# PG03_Schematic_Sheet1_ECO.net
KiCad netlist of a schematic drawn in Altium Designer
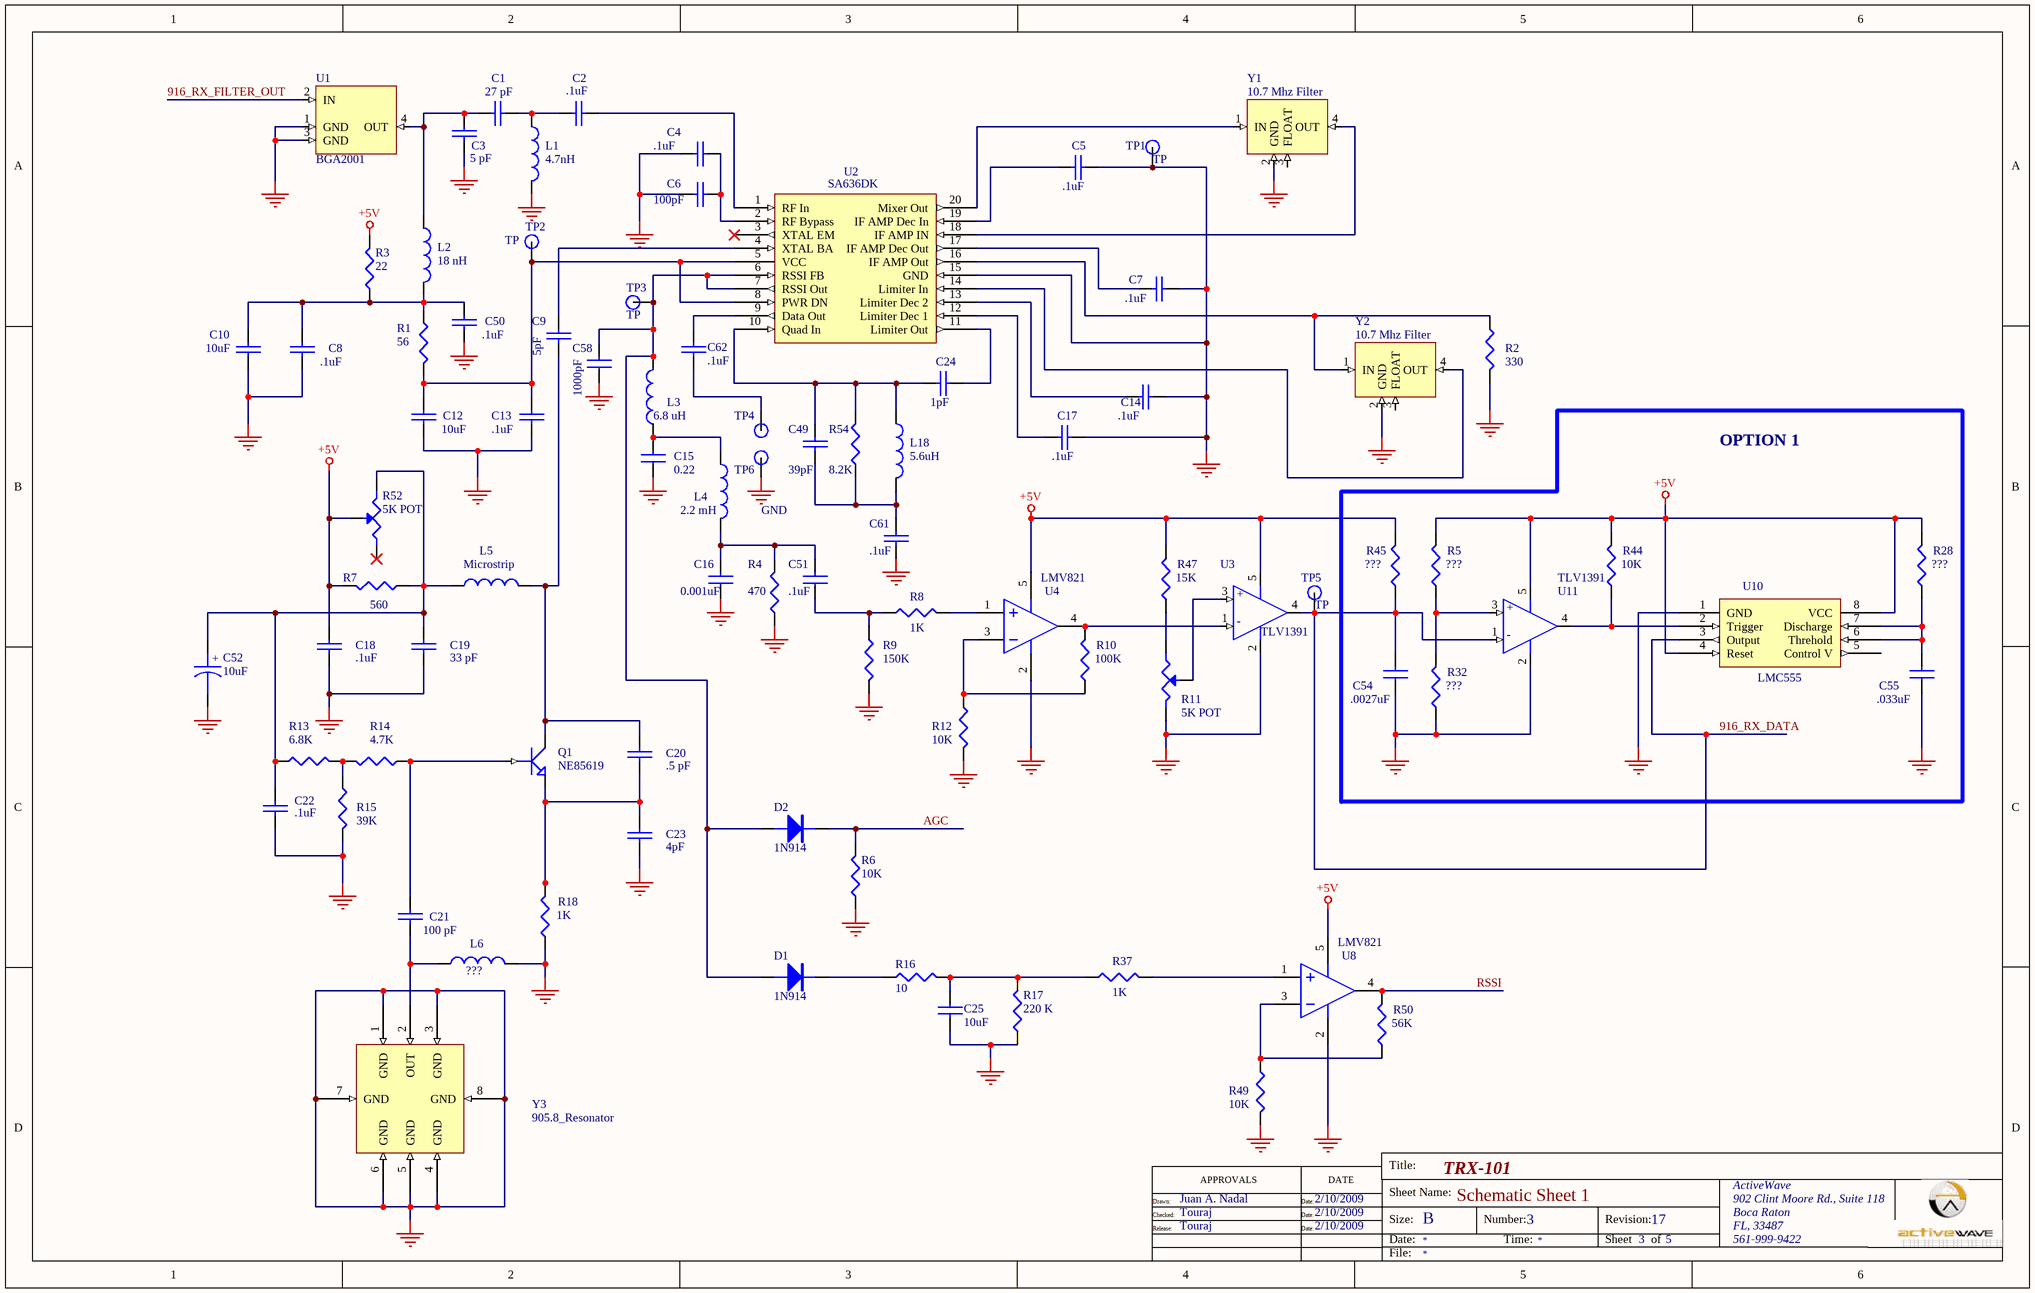
[diagram p0: PG03_Schematic Sheet1_ECO.SchDoc]

(export (version "E")
  (design (tool "Eeschema 10.0.6"))
  (components
    (comp (ref "C1")
      (value "27 pF")
      (footprint "0603")
      (description "Capacitor")
      (libsource (lib "*") (part "CAP"))
    )
    (comp (ref "C2")
      (value ".1uF")
      (footprint "0603")
      (description "Capacitor")
      (libsource (lib "*") (part "CAP"))
    )
    (comp (ref "C3")
      (value "5 pF")
      (footprint "0603")
      (description "Capacitor")
      (libsource (lib "*") (part "CAP"))
    )
    (comp (ref "C4")
      (value ".1uF")
      (footprint "0603")
      (description "Capacitor")
      (libsource (lib "*") (part "CAP"))
    )
    (comp (ref "C5")
      (value ".1uF")
      (footprint "0603")
      (description "Capacitor")
      (libsource (lib "*") (part "CAP"))
    )
    (comp (ref "C6")
      (value "100pF")
      (footprint "0603")
      (description "Capacitor")
      (libsource (lib "*") (part "CAP"))
    )
    (comp (ref "C7")
      (value ".1uF")
      (footprint "0603")
      (description "Capacitor")
      (libsource (lib "*") (part "CAP"))
    )
    (comp (ref "C8")
      (value ".1uF")
      (footprint "0603")
      (description "Capacitor")
      (libsource (lib "*") (part "CAP"))
    )
    (comp (ref "C9")
      (value "5pF")
      (footprint "0603")
      (description "Capacitor")
      (libsource (lib "*") (part "CAP"))
    )
    (comp (ref "C10")
      (value "10uF")
      (footprint "CAP A CASE")
      (description "Capacitor")
      (libsource (lib "*") (part "CAP"))
    )
    (comp (ref "C12")
      (value "10uF")
      (footprint "CAP A CASE")
      (description "Capacitor")
      (libsource (lib "*") (part "CAP"))
    )
    (comp (ref "C13")
      (value ".1uF")
      (footprint "0603")
      (description "Capacitor")
      (libsource (lib "*") (part "CAP"))
    )
    (comp (ref "C14")
      (value ".1uF")
      (footprint "0603")
      (description "Capacitor")
      (libsource (lib "*") (part "CAP"))
    )
    (comp (ref "C15") (value "0.22") (footprint "0603") (libsource (lib "*") (part "CAP_NP")))
    (comp (ref "C16") (value "0.001uF") (footprint "0603") (libsource (lib "*") (part "CAP_NP")))
    (comp (ref "C17")
      (value ".1uF")
      (footprint "0603")
      (description "Capacitor")
      (libsource (lib "*") (part "CAP"))
    )
    (comp (ref "C18")
      (value ".1uF")
      (footprint "0603")
      (description "Capacitor")
      (libsource (lib "*") (part "CAP"))
    )
    (comp (ref "C19")
      (value "33 pF")
      (footprint "0603")
      (description "Capacitor")
      (libsource (lib "*") (part "CAP"))
    )
    (comp (ref "C20")
      (value ".5 pF")
      (footprint "0603")
      (description "Capacitor")
      (libsource (lib "*") (part "CAP"))
    )
    (comp (ref "C21")
      (value "100 pF")
      (footprint "0603")
      (description "Capacitor")
      (libsource (lib "*") (part "CAP"))
    )
    (comp (ref "C22")
      (value ".1uF")
      (footprint "0603")
      (description "Capacitor")
      (libsource (lib "*") (part "CAP"))
    )
    (comp (ref "C23")
      (value "4pF")
      (footprint "0603")
      (description "Capacitor")
      (libsource (lib "*") (part "CAP"))
    )
    (comp (ref "C24")
      (value "1pF")
      (footprint "0603")
      (description "Capacitor")
      (libsource (lib "*") (part "CAP"))
    )
    (comp (ref "C25") (value "10uF") (footprint "CAP A CASE") (libsource (lib "*") (part "CAP_NP")))
    (comp (ref "C49")
      (value "39pF")
      (footprint "0603")
      (description "Capacitor")
      (libsource (lib "*") (part "CAP"))
    )
    (comp (ref "C50")
      (value ".1uF")
      (footprint "0603")
      (description "Capacitor")
      (libsource (lib "*") (part "CAP"))
    )
    (comp (ref "C51") (value ".1uF") (footprint "0603") (libsource (lib "*") (part "CAP_NP")))
    (comp (ref "C52")
      (value "10uF")
      (footprint "CAP A CASE")
      (description "Capacitor")
      (libsource (lib "*") (part "CAPACITOR POL"))
    )
    (comp (ref "C54") (value ".0027uF") (footprint "0603") (libsource (lib "*") (part "CAP_NP")))
    (comp (ref "C55") (value ".033uF") (footprint "0805") (libsource (lib "*") (part "CAP_NP")))
    (comp (ref "C58") (value "1000pF") (footprint "0603") (libsource (lib "*") (part "CAP_NP")))
    (comp (ref "C61")
      (value ".1uF")
      (footprint "0603")
      (description "Capacitor")
      (libsource (lib "*") (part "CAP"))
    )
    (comp (ref "C62")
      (value ".1uF")
      (footprint "0603")
      (description "Capacitor")
      (libsource (lib "*") (part "CAP"))
    )
    (comp (ref "D1")
      (value "1N914")
      (footprint "SOT23 DIODE")
      (description "Diode")
      (libsource (lib "*") (part "DIODE"))
    )
    (comp (ref "D2")
      (value "1N914")
      (footprint "SOT23 DIODE")
      (description "Diode")
      (libsource (lib "*") (part "DIODE"))
    )
    (comp (ref "L1") (value "4.7nH") (footprint "0603") (libsource (lib "*") (part "INDUCTOR")))
    (comp (ref "L2") (value "18 nH") (footprint "0603") (libsource (lib "*") (part "INDUCTOR")))
    (comp (ref "L3") (value "6.8 uH") (footprint "0805") (libsource (lib "*") (part "INDUCTOR")))
    (comp (ref "L4") (value "2.2 mH") (footprint "COIL TKS5540CT-ND") (libsource (lib "*") (part "INDUCTOR")))
    (comp (ref "L5") (value "Microstrip") (footprint "MICROSTRIP") (libsource (lib "*") (part "INDUCTOR")))
    (comp (ref "L6") (value "???") (footprint "0603") (libsource (lib "*") (part "INDUCTOR")))
    (comp (ref "L18") (value "5.6uH") (footprint "0603") (libsource (lib "*") (part "INDUCTOR")))
    (comp (ref "Q1")
      (value "NE85619")
      (footprint "3 PIN ULTRA SUPER MINI MOLD")
      (description "NPN Transistor")
      (libsource (lib "*") (part "NPN1"))
    )
    (comp (ref "R1") (value "56") (footprint "0603") (libsource (lib "*") (part "R")))
    (comp (ref "R2") (value "330") (footprint "0603") (libsource (lib "*") (part "R")))
    (comp (ref "R3") (value "22") (footprint "0603") (libsource (lib "*") (part "R")))
    (comp (ref "R4") (value "470") (footprint "0603") (libsource (lib "*") (part "R")))
    (comp (ref "R5") (value "???") (footprint "0603") (libsource (lib "*") (part "R")))
    (comp (ref "R6") (value "10K") (footprint "0603") (libsource (lib "*") (part "R")))
    (comp (ref "R7") (value "560") (footprint "0603") (libsource (lib "*") (part "RESISTOR")))
    (comp (ref "R8") (value "1K") (footprint "0603") (libsource (lib "*") (part "R")))
    (comp (ref "R9") (value "150K") (footprint "0603") (libsource (lib "*") (part "R")))
    (comp (ref "R10") (value "100K") (footprint "0603") (libsource (lib "*") (part "R")))
    (comp (ref "R11")
      (value "5K POT")
      (footprint "POT PANA EVN5")
      (description "Potentiometer")
      (libsource (lib "") (part "POT1_1"))
    )
    (comp (ref "R12") (value "10K") (footprint "0603") (libsource (lib "*") (part "R")))
    (comp (ref "R13") (value "6.8K") (footprint "0603") (libsource (lib "*") (part "RESISTOR")))
    (comp (ref "R14") (value "4.7K") (footprint "0603") (libsource (lib "*") (part "RESISTOR")))
    (comp (ref "R15") (value "39K") (footprint "0603") (libsource (lib "*") (part "RESISTOR")))
    (comp (ref "R16") (value "10") (footprint "0603") (libsource (lib "*") (part "R")))
    (comp (ref "R17") (value "220 K") (footprint "0603") (libsource (lib "*") (part "R")))
    (comp (ref "R18") (value "1K") (footprint "0603") (libsource (lib "*") (part "RESISTOR")))
    (comp (ref "R28") (value "???") (footprint "0603") (libsource (lib "*") (part "R")))
    (comp (ref "R32") (value "???") (footprint "0603") (libsource (lib "*") (part "R")))
    (comp (ref "R37") (value "1K") (footprint "0603") (libsource (lib "*") (part "R")))
    (comp (ref "R44") (value "10K") (footprint "0603") (libsource (lib "*") (part "R")))
    (comp (ref "R45") (value "???") (footprint "0603") (libsource (lib "*") (part "R")))
    (comp (ref "R47") (value "15K") (footprint "0603") (libsource (lib "*") (part "R")))
    (comp (ref "R49") (value "10K") (footprint "0603") (libsource (lib "*") (part "R")))
    (comp (ref "R50") (value "56K") (footprint "0603") (libsource (lib "*") (part "R")))
    (comp (ref "R52")
      (value "5K POT")
      (footprint "POT PANA EVN5")
      (description "Potentiometer")
      (libsource (lib "*") (part "POT1"))
    )
    (comp (ref "R54") (value "8.2K") (footprint "0603") (libsource (lib "*") (part "R")))
    (comp (ref "TP1") (value "TP") (footprint "TESTPOINT") (libsource (lib "TRX-101R16") (part "TP")))
    (comp (ref "TP2") (value "TP") (footprint "TESTPOINT") (libsource (lib "TRX-101R16") (part "TP")))
    (comp (ref "TP3") (value "TP") (footprint "TESTPOINT") (libsource (lib "TRX-101R16") (part "TP")))
    (comp (ref "TP4") (value "TP") (footprint "TESTPOINT") (libsource (lib "TRX-101R16") (part "TP")))
    (comp (ref "TP5") (value "TP") (footprint "TESTPOINT") (libsource (lib "TRX-101R16") (part "TP")))
    (comp (ref "TP6") (value "GND") (footprint "TESTPOINT") (libsource (lib "TRX-101R16") (part "TP")))
    (comp (ref "U1") (value "BGA2001") (footprint "SOT343") (libsource (lib "*") (part "BGA2001")))
    (comp (ref "U2") (value "SA636DK") (footprint "SSOP20") (libsource (lib "*") (part "SA636DK")))
    (comp (ref "U3") (value "TLV1391") (footprint "SOT25") (libsource (lib "*") (part "TLV1391")))
    (comp (ref "U4") (value "LMV821") (footprint "SOT25") (libsource (lib "*") (part "OPAMP1")))
    (comp (ref "U8") (value "LMV821") (footprint "SOT25") (libsource (lib "*") (part "OPAMP1")))
    (comp (ref "U10") (value "LMC555") (footprint "SO8 SMALL") (libsource (lib "*") (part "LMC555")))
    (comp (ref "U11") (value "TLV1391") (footprint "SOT25") (libsource (lib "*") (part "TLV1391")))
    (comp (ref "Y1") (value "10.7 Mhz Filter") (footprint "FILTER2") (libsource (lib "*") (part "FILTER2")))
    (comp (ref "Y2") (value "10.7 Mhz Filter") (footprint "FILTER2") (libsource (lib "*") (part "FILTER2")))
    (comp (ref "Y3")
      (value "905.8_Resonator")
      (footprint "RESONATOR")
      (libsource (lib "TRX-101_16") (part "RESONATOR2"))
    )
  )
  (nets
    (net (code "1") (name "+5V") (class "Default")
      (node (ref "C18") (pin "1") (pinfunction "1_1") (pintype "passive"))
      (node (ref "R28") (pin "2") (pinfunction "2_2") (pintype "passive"))
      (node (ref "R3") (pin "2") (pinfunction "2_2") (pintype "passive"))
      (node (ref "R44") (pin "2") (pinfunction "2_2") (pintype "passive"))
      (node (ref "R45") (pin "2") (pinfunction "2_2") (pintype "passive"))
      (node (ref "R47") (pin "2") (pinfunction "2_2") (pintype "passive"))
      (node (ref "R5") (pin "2") (pinfunction "2_2") (pintype "passive"))
      (node (ref "R52") (pin "2") (pinfunction "2_2") (pintype "passive"))
      (node (ref "R7") (pin "2") (pinfunction "2_2") (pintype "passive"))
      (node (ref "U10") (pin "4") (pinfunction "Reset_4") (pintype "input"))
      (node (ref "U10") (pin "8") (pinfunction "VCC_8") (pintype "power_in"))
      (node (ref "U11") (pin "5") (pinfunction "VDD_5") (pintype "power_in"))
      (node (ref "U3") (pin "5") (pinfunction "VDD_5") (pintype "power_in"))
      (node (ref "U4") (pin "5") (pinfunction "5_5") (pintype "passive"))
      (node (ref "U8") (pin "5") (pinfunction "5_5") (pintype "passive"))
    )
    (net (code "2") (name "/916_RX_DATA") (class "Default")
      (node (ref "C54") (pin "2") (pinfunction "2_2") (pintype "passive"))
      (node (ref "R45") (pin "1") (pinfunction "1_1") (pintype "passive"))
      (node (ref "TP5") (pin "1") (pinfunction "TP_1") (pintype "passive"))
      (node (ref "U10") (pin "3") (pinfunction "Output_3") (pintype "output"))
      (node (ref "U11") (pin "1") (pinfunction "-_1") (pintype "input"))
      (node (ref "U3") (pin "4") (pinfunction "OUT_4") (pintype "open_collector"))
    )
    (net (code "3") (name "/916_RX_FILTER_OUT") (class "Default")
      (node (ref "U1") (pin "2") (pinfunction "IN_2") (pintype "input"))
    )
    (net (code "4") (name "/AGC") (class "Default")
      (node (ref "D2") (pin "K") (pinfunction "K_K") (pintype "passive"))
      (node (ref "R6") (pin "1") (pinfunction "1_1") (pintype "passive"))
    )
    (net (code "5") (name "/RSSI") (class "Default")
      (node (ref "R50") (pin "2") (pinfunction "2_2") (pintype "passive"))
      (node (ref "U8") (pin "4") (pinfunction "4_4") (pintype "passive"))
    )
    (net (code "6") (name "GND_SIGNAL") (class "Default")
      (node (ref "C10") (pin "2") (pinfunction "2_2") (pintype "passive"))
      (node (ref "C12") (pin "2") (pinfunction "2_2") (pintype "passive"))
      (node (ref "C13") (pin "2") (pinfunction "2_2") (pintype "passive"))
      (node (ref "C14") (pin "2") (pinfunction "2_2") (pintype "passive"))
      (node (ref "C15") (pin "1") (pinfunction "1_1") (pintype "passive"))
      (node (ref "C16") (pin "1") (pinfunction "1_1") (pintype "passive"))
      (node (ref "C17") (pin "2") (pinfunction "2_2") (pintype "passive"))
      (node (ref "C18") (pin "2") (pinfunction "2_2") (pintype "passive"))
      (node (ref "C19") (pin "2") (pinfunction "2_2") (pintype "passive"))
      (node (ref "C22") (pin "2") (pinfunction "2_2") (pintype "passive"))
      (node (ref "C23") (pin "2") (pinfunction "2_2") (pintype "passive"))
      (node (ref "C25") (pin "2") (pinfunction "2_2") (pintype "passive"))
      (node (ref "C3") (pin "2") (pinfunction "2_2") (pintype "passive"))
      (node (ref "C4") (pin "1") (pinfunction "1_1") (pintype "passive"))
      (node (ref "C5") (pin "2") (pinfunction "2_2") (pintype "passive"))
      (node (ref "C50") (pin "2") (pinfunction "2_2") (pintype "passive"))
      (node (ref "C52") (pin "2") (pinfunction "2_2") (pintype "passive"))
      (node (ref "C54") (pin "1") (pinfunction "1_1") (pintype "passive"))
      (node (ref "C55") (pin "1") (pinfunction "1_1") (pintype "passive"))
      (node (ref "C58") (pin "1") (pinfunction "1_1") (pintype "passive"))
      (node (ref "C6") (pin "1") (pinfunction "1_1") (pintype "passive"))
      (node (ref "C61") (pin "2") (pinfunction "2_2") (pintype "passive"))
      (node (ref "C7") (pin "2") (pinfunction "2_2") (pintype "passive"))
      (node (ref "C8") (pin "2") (pinfunction "2_2") (pintype "passive"))
      (node (ref "L1") (pin "2") (pinfunction "2_2") (pintype "passive"))
      (node (ref "L6") (pin "2") (pinfunction "2_2") (pintype "passive"))
      (node (ref "R11") (pin "3") (pinfunction "3_3") (pintype "passive"))
      (node (ref "R12") (pin "2") (pinfunction "2_2") (pintype "passive"))
      (node (ref "R15") (pin "2") (pinfunction "2_2") (pintype "passive"))
      (node (ref "R17") (pin "2") (pinfunction "2_2") (pintype "passive"))
      (node (ref "R18") (pin "1") (pinfunction "1_1") (pintype "passive"))
      (node (ref "R2") (pin "2") (pinfunction "2_2") (pintype "passive"))
      (node (ref "R32") (pin "1") (pinfunction "1_1") (pintype "passive"))
      (node (ref "R4") (pin "1") (pinfunction "1_1") (pintype "passive"))
      (node (ref "R49") (pin "2") (pinfunction "2_2") (pintype "passive"))
      (node (ref "R6") (pin "2") (pinfunction "2_2") (pintype "passive"))
      (node (ref "R9") (pin "2") (pinfunction "2_2") (pintype "passive"))
      (node (ref "TP1") (pin "1") (pinfunction "TP_1") (pintype "passive"))
      (node (ref "TP6") (pin "1") (pinfunction "TP_1") (pintype "passive"))
      (node (ref "U1") (pin "1") (pinfunction "GND_1") (pintype "input"))
      (node (ref "U1") (pin "3") (pinfunction "GND_3") (pintype "input"))
      (node (ref "U10") (pin "1") (pinfunction "GND_1") (pintype "power_in"))
      (node (ref "U11") (pin "2") (pinfunction "VSS_2") (pintype "power_in"))
      (node (ref "U2") (pin "15") (pinfunction "GND_15") (pintype "input"))
      (node (ref "U3") (pin "2") (pinfunction "VSS_2") (pintype "power_in"))
      (node (ref "U4") (pin "2") (pinfunction "2_2") (pintype "passive"))
      (node (ref "U8") (pin "2") (pinfunction "2_2") (pintype "passive"))
      (node (ref "Y1") (pin "2") (pinfunction "GND_2") (pintype "input"))
      (node (ref "Y2") (pin "2") (pinfunction "GND_2") (pintype "input"))
      (node (ref "Y3") (pin "1") (pinfunction "GND_1") (pintype "input"))
      (node (ref "Y3") (pin "3") (pinfunction "GND_3") (pintype "input"))
      (node (ref "Y3") (pin "4") (pinfunction "GND_4") (pintype "input"))
      (node (ref "Y3") (pin "5") (pinfunction "GND_5") (pintype "input"))
      (node (ref "Y3") (pin "6") (pinfunction "GND_6") (pintype "input"))
      (node (ref "Y3") (pin "7") (pinfunction "GND_7") (pintype "input"))
      (node (ref "Y3") (pin "8") (pinfunction "GND_8") (pintype "input"))
    )
    (net (code "7") (name "Net-(C1-Pad2)") (class "Default")
      (node (ref "C1") (pin "2") (pinfunction "2_2") (pintype "passive"))
      (node (ref "C2") (pin "1") (pinfunction "1_1") (pintype "passive"))
      (node (ref "L1") (pin "1") (pinfunction "1_1") (pintype "passive"))
    )
    (net (code "8") (name "Net-(C10-Pad1)") (class "Default")
      (node (ref "C10") (pin "1") (pinfunction "1_1") (pintype "passive"))
      (node (ref "C50") (pin "1") (pinfunction "1_1") (pintype "passive"))
      (node (ref "C8") (pin "1") (pinfunction "1_1") (pintype "passive"))
      (node (ref "L2") (pin "2") (pinfunction "2_2") (pintype "passive"))
      (node (ref "R1") (pin "1") (pinfunction "1_1") (pintype "passive"))
      (node (ref "R3") (pin "1") (pinfunction "1_1") (pintype "passive"))
    )
    (net (code "9") (name "Net-(C15-Pad2)") (class "Default")
      (node (ref "C15") (pin "2") (pinfunction "2_2") (pintype "passive"))
      (node (ref "L3") (pin "1") (pinfunction "1_1") (pintype "passive"))
      (node (ref "L4") (pin "1") (pinfunction "1_1") (pintype "passive"))
    )
    (net (code "10") (name "Net-(C16-Pad2)") (class "Default")
      (node (ref "C16") (pin "2") (pinfunction "2_2") (pintype "passive"))
      (node (ref "C51") (pin "2") (pinfunction "2_2") (pintype "passive"))
      (node (ref "L4") (pin "2") (pinfunction "2_2") (pintype "passive"))
      (node (ref "R4") (pin "2") (pinfunction "2_2") (pintype "passive"))
    )
    (net (code "11") (name "Net-(C19-Pad1)") (class "Default")
      (node (ref "C19") (pin "1") (pinfunction "1_1") (pintype "passive"))
      (node (ref "C22") (pin "1") (pinfunction "1_1") (pintype "passive"))
      (node (ref "C52") (pin "1") (pinfunction "1_1") (pintype "passive"))
      (node (ref "L5") (pin "1") (pinfunction "1_1") (pintype "passive"))
      (node (ref "R13") (pin "1") (pinfunction "1_1") (pintype "passive"))
      (node (ref "R52") (pin "1") (pinfunction "1_1") (pintype "passive"))
      (node (ref "R7") (pin "1") (pinfunction "1_1") (pintype "passive"))
    )
    (net (code "12") (name "Net-(C20-Pad1)") (class "Default")
      (node (ref "C20") (pin "1") (pinfunction "1_1") (pintype "passive"))
      (node (ref "C9") (pin "1") (pinfunction "1_1") (pintype "passive"))
      (node (ref "L5") (pin "2") (pinfunction "2_2") (pintype "passive"))
      (node (ref "Q1") (pin "C") (pinfunction "C_C") (pintype "passive"))
    )
    (net (code "13") (name "Net-(C20-Pad2)") (class "Default")
      (node (ref "C20") (pin "2") (pinfunction "2_2") (pintype "passive"))
      (node (ref "C23") (pin "1") (pinfunction "1_1") (pintype "passive"))
      (node (ref "Q1") (pin "E") (pinfunction "E_E") (pintype "passive"))
      (node (ref "R18") (pin "2") (pinfunction "2_2") (pintype "passive"))
    )
    (net (code "14") (name "Net-(C21-Pad1)") (class "Default")
      (node (ref "C21") (pin "1") (pinfunction "1_1") (pintype "passive"))
      (node (ref "Q1") (pin "B") (pinfunction "B_B") (pintype "input"))
      (node (ref "R14") (pin "1") (pinfunction "1_1") (pintype "passive"))
    )
    (net (code "15") (name "Net-(C25-Pad1)") (class "Default")
      (node (ref "C25") (pin "1") (pinfunction "1_1") (pintype "passive"))
      (node (ref "R16") (pin "1") (pinfunction "1_1") (pintype "passive"))
      (node (ref "R17") (pin "1") (pinfunction "1_1") (pintype "passive"))
      (node (ref "R37") (pin "1") (pinfunction "1_1") (pintype "passive"))
    )
    (net (code "16") (name "Net-(C49-Pad2)") (class "Default")
      (node (ref "C49") (pin "2") (pinfunction "2_2") (pintype "passive"))
      (node (ref "C61") (pin "1") (pinfunction "1_1") (pintype "passive"))
      (node (ref "L18") (pin "2") (pinfunction "2_2") (pintype "passive"))
      (node (ref "R54") (pin "1") (pinfunction "1_1") (pintype "passive"))
    )
    (net (code "17") (name "Net-(C51-Pad1)") (class "Default")
      (node (ref "C51") (pin "1") (pinfunction "1_1") (pintype "passive"))
      (node (ref "R8") (pin "1") (pinfunction "1_1") (pintype "passive"))
      (node (ref "R9") (pin "1") (pinfunction "1_1") (pintype "passive"))
    )
    (net (code "18") (name "Net-(D1-PadK)") (class "Default")
      (node (ref "D1") (pin "K") (pinfunction "K_K") (pintype "passive"))
      (node (ref "R16") (pin "2") (pinfunction "2_2") (pintype "passive"))
    )
    (net (code "19") (name "Net-(R8-Pad2)") (class "Default")
      (node (ref "R8") (pin "2") (pinfunction "2_2") (pintype "passive"))
      (node (ref "U4") (pin "1") (pinfunction "1_1") (pintype "passive"))
    )
    (net (code "20") (name "Net-(R10-Pad1)") (class "Default")
      (node (ref "R10") (pin "1") (pinfunction "1_1") (pintype "passive"))
      (node (ref "R12") (pin "1") (pinfunction "1_1") (pintype "passive"))
      (node (ref "U4") (pin "3") (pinfunction "3_3") (pintype "passive"))
    )
    (net (code "21") (name "Net-(R11-Pad1)") (class "Default")
      (node (ref "R11") (pin "1") (pinfunction "1_1") (pintype "passive"))
      (node (ref "R47") (pin "1") (pinfunction "1_1") (pintype "passive"))
    )
    (net (code "22") (name "Net-(R13-Pad2)") (class "Default")
      (node (ref "R13") (pin "2") (pinfunction "2_2") (pintype "passive"))
      (node (ref "R14") (pin "2") (pinfunction "2_2") (pintype "passive"))
      (node (ref "R15") (pin "1") (pinfunction "1_1") (pintype "passive"))
    )
    (net (code "23") (name "Net-(R37-Pad2)") (class "Default")
      (node (ref "R37") (pin "2") (pinfunction "2_2") (pintype "passive"))
      (node (ref "U8") (pin "1") (pinfunction "1_1") (pintype "passive"))
    )
    (net (code "24") (name "Net-(R49-Pad1)") (class "Default")
      (node (ref "R49") (pin "1") (pinfunction "1_1") (pintype "passive"))
      (node (ref "R50") (pin "1") (pinfunction "1_1") (pintype "passive"))
      (node (ref "U8") (pin "3") (pinfunction "3_3") (pintype "passive"))
    )
    (net (code "25") (name "Net-(TP2-TP)") (class "Default")
      (node (ref "C12") (pin "1") (pinfunction "1_1") (pintype "passive"))
      (node (ref "C13") (pin "1") (pinfunction "1_1") (pintype "passive"))
      (node (ref "R1") (pin "2") (pinfunction "2_2") (pintype "passive"))
      (node (ref "TP2") (pin "1") (pinfunction "TP_1") (pintype "passive"))
      (node (ref "U2") (pin "5") (pinfunction "VCC_5") (pintype "power_in"))
      (node (ref "U2") (pin "8") (pinfunction "PWR_DN_8") (pintype "input"))
    )
    (net (code "26") (name "Net-(TP3-TP)") (class "Default")
      (node (ref "C58") (pin "2") (pinfunction "2_2") (pintype "passive"))
      (node (ref "D1") (pin "A") (pinfunction "A_A") (pintype "passive"))
      (node (ref "D2") (pin "A") (pinfunction "A_A") (pintype "passive"))
      (node (ref "L3") (pin "2") (pinfunction "2_2") (pintype "passive"))
      (node (ref "TP3") (pin "1") (pinfunction "TP_1") (pintype "passive"))
      (node (ref "U2") (pin "6") (pinfunction "RSSI_FB_6") (pintype "input"))
      (node (ref "U2") (pin "7") (pinfunction "RSSI_Out_7") (pintype "output"))
    )
    (net (code "27") (name "Net-(TP4-TP)") (class "Default")
      (node (ref "C62") (pin "1") (pinfunction "1_1") (pintype "passive"))
      (node (ref "TP4") (pin "1") (pinfunction "TP_1") (pintype "passive"))
    )
    (net (code "28") (name "Net-(U1-OUT)") (class "Default")
      (node (ref "C1") (pin "1") (pinfunction "1_1") (pintype "passive"))
      (node (ref "C3") (pin "1") (pinfunction "1_1") (pintype "passive"))
      (node (ref "L2") (pin "1") (pinfunction "1_1") (pintype "passive"))
      (node (ref "U1") (pin "4") (pinfunction "OUT_4") (pintype "input"))
    )
    (net (code "29") (name "Net-(U2-Data_Out)") (class "Default")
      (node (ref "C62") (pin "2") (pinfunction "2_2") (pintype "passive"))
      (node (ref "U2") (pin "9") (pinfunction "Data_Out_9") (pintype "output"))
    )
    (net (code "30") (name "Net-(U2-IF_AMP_Dec_In)") (class "Default")
      (node (ref "C5") (pin "1") (pinfunction "1_1") (pintype "passive"))
      (node (ref "U2") (pin "19") (pinfunction "IF_AMP_Dec_In_19") (pintype "input"))
    )
    (net (code "31") (name "Net-(U2-IF_AMP_Dec_Out)") (class "Default")
      (node (ref "C7") (pin "1") (pinfunction "1_1") (pintype "passive"))
      (node (ref "U2") (pin "17") (pinfunction "IF_AMP_Dec_Out_17") (pintype "output"))
    )
    (net (code "32") (name "Net-(U2-IF_AMP_IN)") (class "Default")
      (node (ref "U2") (pin "18") (pinfunction "IF_AMP_IN_18") (pintype "input"))
      (node (ref "Y1") (pin "4") (pinfunction "OUT_4") (pintype "input"))
    )
    (net (code "33") (name "Net-(U2-IF_AMP_Out)") (class "Default")
      (node (ref "R2") (pin "1") (pinfunction "1_1") (pintype "passive"))
      (node (ref "U2") (pin "16") (pinfunction "IF_AMP_Out_16") (pintype "output"))
      (node (ref "Y2") (pin "1") (pinfunction "IN_1") (pintype "input"))
    )
    (net (code "34") (name "Net-(U2-Limiter_Dec_1)") (class "Default")
      (node (ref "C17") (pin "1") (pinfunction "1_1") (pintype "passive"))
      (node (ref "U2") (pin "12") (pinfunction "Limiter_Dec_1_12") (pintype "input"))
    )
    (net (code "35") (name "Net-(U2-Limiter_Dec_2)") (class "Default")
      (node (ref "C14") (pin "1") (pinfunction "1_1") (pintype "passive"))
      (node (ref "U2") (pin "13") (pinfunction "Limiter_Dec_2_13") (pintype "input"))
    )
    (net (code "36") (name "Net-(U2-Limiter_In)") (class "Default")
      (node (ref "U2") (pin "14") (pinfunction "Limiter_In_14") (pintype "input"))
      (node (ref "Y2") (pin "4") (pinfunction "OUT_4") (pintype "input"))
    )
    (net (code "37") (name "Net-(U2-Limiter_Out)") (class "Default")
      (node (ref "C24") (pin "2") (pinfunction "2_2") (pintype "passive"))
      (node (ref "U2") (pin "11") (pinfunction "Limiter_Out_11") (pintype "output"))
    )
    (net (code "38") (name "Net-(U2-Mixer_Out)") (class "Default")
      (node (ref "U2") (pin "20") (pinfunction "Mixer_Out_20") (pintype "output"))
      (node (ref "Y1") (pin "1") (pinfunction "IN_1") (pintype "input"))
    )
    (net (code "39") (name "Net-(U2-Quad_In)") (class "Default")
      (node (ref "C24") (pin "1") (pinfunction "1_1") (pintype "passive"))
      (node (ref "C49") (pin "1") (pinfunction "1_1") (pintype "passive"))
      (node (ref "L18") (pin "1") (pinfunction "1_1") (pintype "passive"))
      (node (ref "R54") (pin "2") (pinfunction "2_2") (pintype "passive"))
      (node (ref "U2") (pin "10") (pinfunction "Quad_In_10") (pintype "input"))
    )
    (net (code "40") (name "Net-(U2-RF_Bypass)") (class "Default")
      (node (ref "C4") (pin "2") (pinfunction "2_2") (pintype "passive"))
      (node (ref "C6") (pin "2") (pinfunction "2_2") (pintype "passive"))
      (node (ref "U2") (pin "2") (pinfunction "RF_Bypass_2") (pintype "input"))
    )
    (net (code "41") (name "Net-(U2-RF_In)") (class "Default")
      (node (ref "C2") (pin "2") (pinfunction "2_2") (pintype "passive"))
      (node (ref "U2") (pin "1") (pinfunction "RF_In_1") (pintype "input"))
    )
    (net (code "42") (name "Net-(U2-XTAL_BA)") (class "Default")
      (node (ref "C9") (pin "2") (pinfunction "2_2") (pintype "passive"))
      (node (ref "U2") (pin "4") (pinfunction "XTAL_BA_4") (pintype "input"))
    )
    (net (code "43") (name "Net-(U3-+)") (class "Default")
      (node (ref "R11") (pin "2") (pinfunction "2_2") (pintype "passive"))
      (node (ref "U3") (pin "3") (pinfunction "+_3") (pintype "input"))
    )
    (net (code "44") (name "Net-(U3--)") (class "Default")
      (node (ref "R10") (pin "2") (pinfunction "2_2") (pintype "passive"))
      (node (ref "U3") (pin "1") (pinfunction "-_1") (pintype "input"))
      (node (ref "U4") (pin "4") (pinfunction "4_4") (pintype "passive"))
    )
    (net (code "45") (name "Net-(U10-Discharge)") (class "Default")
      (node (ref "C55") (pin "2") (pinfunction "2_2") (pintype "passive"))
      (node (ref "R28") (pin "1") (pinfunction "1_1") (pintype "passive"))
      (node (ref "U10") (pin "6") (pinfunction "Threhold_6") (pintype "input"))
      (node (ref "U10") (pin "7") (pinfunction "Discharge_7") (pintype "input"))
    )
    (net (code "46") (name "Net-(U10-Trigger)") (class "Default")
      (node (ref "R44") (pin "1") (pinfunction "1_1") (pintype "passive"))
      (node (ref "U10") (pin "2") (pinfunction "Trigger_2") (pintype "input"))
      (node (ref "U11") (pin "4") (pinfunction "OUT_4") (pintype "open_collector"))
    )
    (net (code "47") (name "Net-(U11-+)") (class "Default")
      (node (ref "R32") (pin "2") (pinfunction "2_2") (pintype "passive"))
      (node (ref "R5") (pin "1") (pinfunction "1_1") (pintype "passive"))
      (node (ref "U11") (pin "3") (pinfunction "+_3") (pintype "input"))
    )
    (net (code "48") (name "Net-(Y3-OUT)") (class "Default")
      (node (ref "C21") (pin "2") (pinfunction "2_2") (pintype "passive"))
      (node (ref "L6") (pin "1") (pinfunction "1_1") (pintype "passive"))
      (node (ref "Y3") (pin "2") (pinfunction "OUT_2") (pintype "input"))
    )
    (net (code "49") (name "unconnected-(R52-Pad3)") (class "Default")
      (node (ref "R52") (pin "3") (pinfunction "3_3") (pintype "passive+no_connect"))
    )
    (net (code "50") (name "unconnected-(U2-XTAL_EM-Pad3)") (class "Default")
      (node (ref "U2") (pin "3") (pinfunction "XTAL_EM_3") (pintype "output+no_connect"))
    )
    (net (code "51") (name "unconnected-(U10-Control_V-Pad5)") (class "Default")
      (node (ref "U10") (pin "5") (pinfunction "Control_V_5") (pintype "output"))
    )
    (net (code "52") (name "unconnected-(Y1-FLOAT-Pad3)") (class "Default")
      (node (ref "Y1") (pin "3") (pinfunction "FLOAT_3") (pintype "input"))
    )
    (net (code "53") (name "unconnected-(Y2-FLOAT-Pad3)") (class "Default")
      (node (ref "Y2") (pin "3") (pinfunction "FLOAT_3") (pintype "input"))
    )
  )
)
